# dms_sensor_board.net
KiCad netlist of a schematic drawn in EAGLE
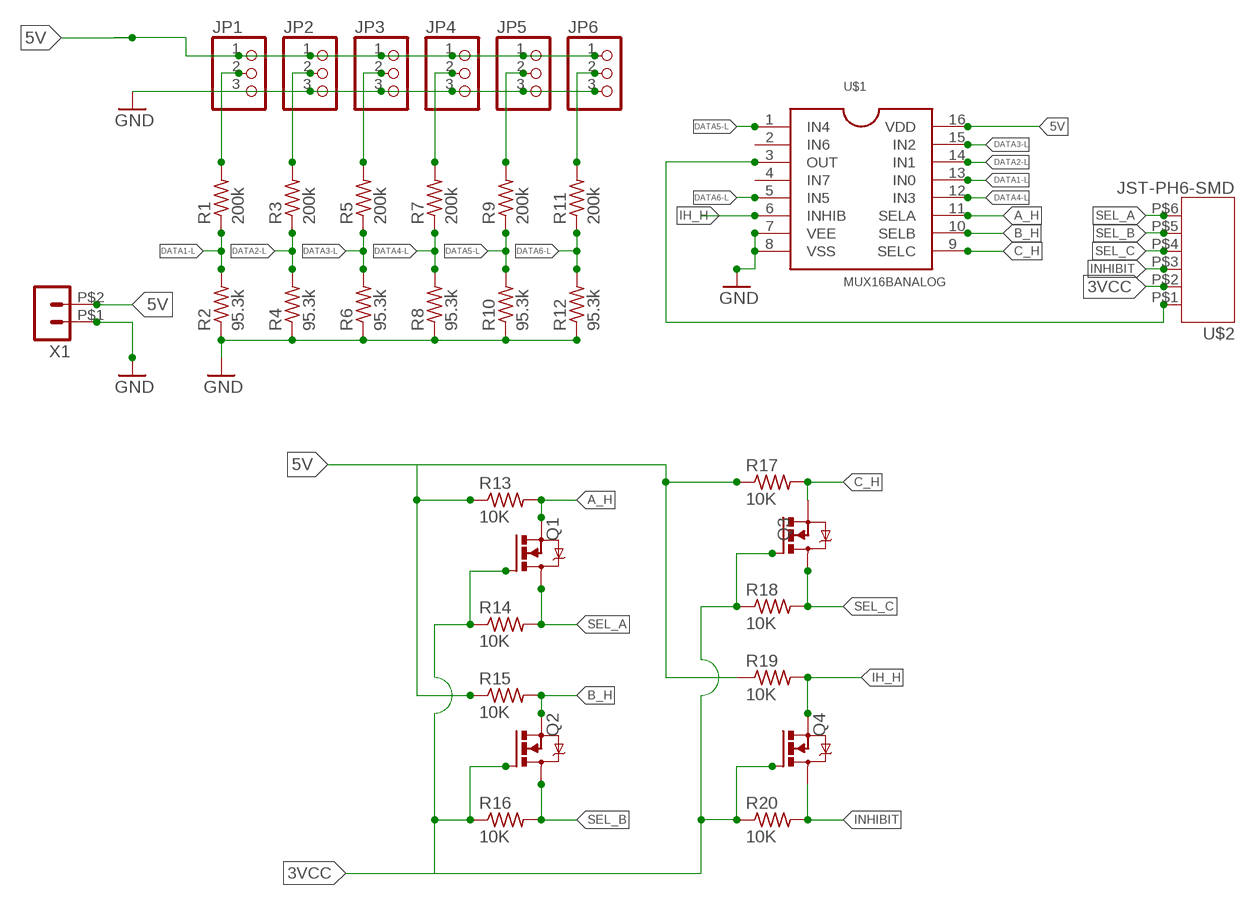
[diagram p0: schematic, sheet 1]

(export (version "E")
  (design (tool "Eeschema 10.0.6"))
  (components
    (comp (ref "JP1")
      (value "PINHD-1X03_2.00")
      (footprint "eagle-import:1X03M")
      (libsource (lib "eagle-import") (part "PINHD-1X03_2.00"))
    )
    (comp (ref "JP2")
      (value "PINHD-1X03_2.00")
      (footprint "eagle-import:1X03M")
      (libsource (lib "eagle-import") (part "PINHD-1X03_2.00"))
    )
    (comp (ref "JP3")
      (value "PINHD-1X03_2.00")
      (footprint "eagle-import:1X03M")
      (libsource (lib "eagle-import") (part "PINHD-1X03_2.00"))
    )
    (comp (ref "JP4")
      (value "PINHD-1X03_2.00")
      (footprint "eagle-import:1X03M")
      (libsource (lib "eagle-import") (part "PINHD-1X03_2.00"))
    )
    (comp (ref "JP5")
      (value "PINHD-1X03_2.00")
      (footprint "eagle-import:1X03M")
      (libsource (lib "eagle-import") (part "PINHD-1X03_2.00"))
    )
    (comp (ref "JP6")
      (value "PINHD-1X03_2.00")
      (footprint "eagle-import:1X03M")
      (libsource (lib "eagle-import") (part "PINHD-1X03_2.00"))
    )
    (comp (ref "Q1")
      (value "IRLML5203")
      (footprint "eagle-import:MICRO3")
      (libsource (lib "eagle-import") (part "IRLML5203"))
    )
    (comp (ref "Q2")
      (value "IRLML5203")
      (footprint "eagle-import:MICRO3")
      (libsource (lib "eagle-import") (part "IRLML5203"))
    )
    (comp (ref "Q3")
      (value "IRLML5203")
      (footprint "eagle-import:MICRO3")
      (libsource (lib "eagle-import") (part "IRLML5203"))
    )
    (comp (ref "Q4")
      (value "IRLML5203")
      (footprint "eagle-import:MICRO3")
      (libsource (lib "eagle-import") (part "IRLML5203"))
    )
    (comp (ref "R1")
      (value "200k")
      (footprint "eagle-import:R0805")
      (libsource (lib "eagle-import") (part "R-US_R0805"))
    )
    (comp (ref "R2")
      (value "95.3k")
      (footprint "eagle-import:R0805")
      (libsource (lib "eagle-import") (part "R-US_R0805"))
    )
    (comp (ref "R3")
      (value "200k")
      (footprint "eagle-import:R0805")
      (libsource (lib "eagle-import") (part "R-US_R0805"))
    )
    (comp (ref "R4")
      (value "95.3k")
      (footprint "eagle-import:R0805")
      (libsource (lib "eagle-import") (part "R-US_R0805"))
    )
    (comp (ref "R5")
      (value "200k")
      (footprint "eagle-import:R0805")
      (libsource (lib "eagle-import") (part "R-US_R0805"))
    )
    (comp (ref "R6")
      (value "95.3k")
      (footprint "eagle-import:R0805")
      (libsource (lib "eagle-import") (part "R-US_R0805"))
    )
    (comp (ref "R7")
      (value "200k")
      (footprint "eagle-import:R0805")
      (libsource (lib "eagle-import") (part "R-US_R0805"))
    )
    (comp (ref "R8")
      (value "95.3k")
      (footprint "eagle-import:R0805")
      (libsource (lib "eagle-import") (part "R-US_R0805"))
    )
    (comp (ref "R9")
      (value "200k")
      (footprint "eagle-import:R0805")
      (libsource (lib "eagle-import") (part "R-US_R0805"))
    )
    (comp (ref "R10")
      (value "95.3k")
      (footprint "eagle-import:R0805")
      (libsource (lib "eagle-import") (part "R-US_R0805"))
    )
    (comp (ref "R11")
      (value "200k")
      (footprint "eagle-import:R0805")
      (libsource (lib "eagle-import") (part "R-US_R0805"))
    )
    (comp (ref "R12")
      (value "95.3k")
      (footprint "eagle-import:R0805")
      (libsource (lib "eagle-import") (part "R-US_R0805"))
    )
    (comp (ref "R13")
      (value "10K")
      (footprint "eagle-import:R0805")
      (libsource (lib "eagle-import") (part "R-US_R0805"))
    )
    (comp (ref "R14")
      (value "10K")
      (footprint "eagle-import:R0805")
      (libsource (lib "eagle-import") (part "R-US_R0805"))
    )
    (comp (ref "R15")
      (value "10K")
      (footprint "eagle-import:R0805")
      (libsource (lib "eagle-import") (part "R-US_R0805"))
    )
    (comp (ref "R16")
      (value "10K")
      (footprint "eagle-import:R0805")
      (libsource (lib "eagle-import") (part "R-US_R0805"))
    )
    (comp (ref "R17")
      (value "10K")
      (footprint "eagle-import:R0805")
      (libsource (lib "eagle-import") (part "R-US_R0805"))
    )
    (comp (ref "R18")
      (value "10K")
      (footprint "eagle-import:R0805")
      (libsource (lib "eagle-import") (part "R-US_R0805"))
    )
    (comp (ref "R19")
      (value "10K")
      (footprint "eagle-import:R0805")
      (libsource (lib "eagle-import") (part "R-US_R0805"))
    )
    (comp (ref "R20")
      (value "10K")
      (footprint "eagle-import:R0805")
      (libsource (lib "eagle-import") (part "R-US_R0805"))
    )
    (comp (ref "U$1")
      (value "MUX16BANALOG")
      (footprint "eagle-import:SO16")
      (libsource (lib "eagle-import") (part "MUX16BANALOG"))
    )
    (comp (ref "U$2")
      (value "JST-PH6-SMD")
      (footprint "eagle-import:JST-PH6-SMD")
      (libsource (lib "eagle-import") (part "JST-PH6-SMD"))
    )
    (comp (ref "X1")
      (value "HEADER_POS2_43045-0206")
      (footprint "eagle-import:43045-0206")
      (libsource (lib "eagle-import") (part "HEADER_POS2_?43045-0206"))
    )
  )
  (nets
    (net (code "1") (name "3VCC") (class "Default")
      (node (ref "Q1") (pin "1") (pinfunction "G_1") (pintype "passive"))
      (node (ref "Q2") (pin "1") (pinfunction "G_1") (pintype "passive"))
      (node (ref "Q3") (pin "1") (pinfunction "G_1") (pintype "passive"))
      (node (ref "Q4") (pin "1") (pinfunction "G_1") (pintype "passive"))
      (node (ref "R14") (pin "1") (pinfunction "1_1") (pintype "passive"))
      (node (ref "R16") (pin "1") (pinfunction "1_1") (pintype "passive"))
      (node (ref "R18") (pin "1") (pinfunction "1_1") (pintype "passive"))
      (node (ref "R20") (pin "1") (pinfunction "1_1") (pintype "passive"))
      (node (ref "U$2") (pin "P$2") (pinfunction "2_P$2") (pintype "passive"))
    )
    (net (code "2") (name "5V") (class "Default")
      (node (ref "JP1") (pin "1") (pinfunction "1_1") (pintype "passive"))
      (node (ref "JP2") (pin "1") (pinfunction "1_1") (pintype "passive"))
      (node (ref "JP3") (pin "1") (pinfunction "1_1") (pintype "passive"))
      (node (ref "JP4") (pin "1") (pinfunction "1_1") (pintype "passive"))
      (node (ref "JP5") (pin "1") (pinfunction "1_1") (pintype "passive"))
      (node (ref "JP6") (pin "1") (pinfunction "1_1") (pintype "passive"))
      (node (ref "R13") (pin "1") (pinfunction "1_1") (pintype "passive"))
      (node (ref "R15") (pin "1") (pinfunction "1_1") (pintype "passive"))
      (node (ref "R17") (pin "1") (pinfunction "1_1") (pintype "passive"))
      (node (ref "R19") (pin "1") (pinfunction "1_1") (pintype "passive"))
      (node (ref "U$1") (pin "16") (pinfunction "VDD_16") (pintype "bidirectional"))
      (node (ref "X1") (pin "P$2") (pinfunction "2_P$2") (pintype "passive"))
    )
    (net (code "3") (name "A_H") (class "Default")
      (node (ref "Q1") (pin "2") (pinfunction "S_2") (pintype "passive"))
      (node (ref "R13") (pin "2") (pinfunction "2_2") (pintype "passive"))
      (node (ref "U$1") (pin "11") (pinfunction "SELA_11") (pintype "bidirectional"))
    )
    (net (code "4") (name "B_H") (class "Default")
      (node (ref "Q2") (pin "2") (pinfunction "S_2") (pintype "passive"))
      (node (ref "R15") (pin "2") (pinfunction "2_2") (pintype "passive"))
      (node (ref "U$1") (pin "10") (pinfunction "SELB_10") (pintype "bidirectional"))
    )
    (net (code "5") (name "C_H") (class "Default")
      (node (ref "Q3") (pin "2") (pinfunction "S_2") (pintype "passive"))
      (node (ref "R17") (pin "2") (pinfunction "2_2") (pintype "passive"))
      (node (ref "U$1") (pin "9") (pinfunction "SELC_9") (pintype "bidirectional"))
    )
    (net (code "6") (name "DATA1-L") (class "Default")
      (node (ref "R1") (pin "1") (pinfunction "1_1") (pintype "passive"))
      (node (ref "R2") (pin "2") (pinfunction "2_2") (pintype "passive"))
      (node (ref "U$1") (pin "13") (pinfunction "IN0_13") (pintype "bidirectional"))
    )
    (net (code "7") (name "DATA2-L") (class "Default")
      (node (ref "R3") (pin "1") (pinfunction "1_1") (pintype "passive"))
      (node (ref "R4") (pin "2") (pinfunction "2_2") (pintype "passive"))
      (node (ref "U$1") (pin "14") (pinfunction "IN1_14") (pintype "bidirectional"))
    )
    (net (code "8") (name "DATA3-L") (class "Default")
      (node (ref "R5") (pin "1") (pinfunction "1_1") (pintype "passive"))
      (node (ref "R6") (pin "2") (pinfunction "2_2") (pintype "passive"))
      (node (ref "U$1") (pin "15") (pinfunction "IN2_15") (pintype "bidirectional"))
    )
    (net (code "9") (name "DATA4-L") (class "Default")
      (node (ref "R7") (pin "1") (pinfunction "1_1") (pintype "passive"))
      (node (ref "R8") (pin "2") (pinfunction "2_2") (pintype "passive"))
      (node (ref "U$1") (pin "12") (pinfunction "IN3_12") (pintype "bidirectional"))
    )
    (net (code "10") (name "DATA5-L") (class "Default")
      (node (ref "R10") (pin "2") (pinfunction "2_2") (pintype "passive"))
      (node (ref "R9") (pin "1") (pinfunction "1_1") (pintype "passive"))
      (node (ref "U$1") (pin "1") (pinfunction "IN4_1") (pintype "bidirectional"))
    )
    (net (code "11") (name "DATA6-L") (class "Default")
      (node (ref "R11") (pin "1") (pinfunction "1_1") (pintype "passive"))
      (node (ref "R12") (pin "2") (pinfunction "2_2") (pintype "passive"))
      (node (ref "U$1") (pin "5") (pinfunction "IN5_5") (pintype "bidirectional"))
    )
    (net (code "12") (name "GND") (class "Default")
      (node (ref "JP1") (pin "3") (pinfunction "3_3") (pintype "passive"))
      (node (ref "JP2") (pin "3") (pinfunction "3_3") (pintype "passive"))
      (node (ref "JP3") (pin "3") (pinfunction "3_3") (pintype "passive"))
      (node (ref "JP4") (pin "3") (pinfunction "3_3") (pintype "passive"))
      (node (ref "JP5") (pin "3") (pinfunction "3_3") (pintype "passive"))
      (node (ref "JP6") (pin "3") (pinfunction "3_3") (pintype "passive"))
      (node (ref "R10") (pin "1") (pinfunction "1_1") (pintype "passive"))
      (node (ref "R12") (pin "1") (pinfunction "1_1") (pintype "passive"))
      (node (ref "R2") (pin "1") (pinfunction "1_1") (pintype "passive"))
      (node (ref "R4") (pin "1") (pinfunction "1_1") (pintype "passive"))
      (node (ref "R6") (pin "1") (pinfunction "1_1") (pintype "passive"))
      (node (ref "R8") (pin "1") (pinfunction "1_1") (pintype "passive"))
      (node (ref "U$1") (pin "7") (pinfunction "VEE_7") (pintype "bidirectional"))
      (node (ref "U$1") (pin "8") (pinfunction "VSS_8") (pintype "bidirectional"))
      (node (ref "X1") (pin "P$1") (pinfunction "1_P$1") (pintype "passive"))
    )
    (net (code "13") (name "IH_H") (class "Default")
      (node (ref "Q4") (pin "2") (pinfunction "S_2") (pintype "passive"))
      (node (ref "R19") (pin "2") (pinfunction "2_2") (pintype "passive"))
      (node (ref "U$1") (pin "6") (pinfunction "INHIB_6") (pintype "bidirectional"))
    )
    (net (code "14") (name "INHIBIT") (class "Default")
      (node (ref "Q4") (pin "3") (pinfunction "D_3") (pintype "passive"))
      (node (ref "R20") (pin "2") (pinfunction "2_2") (pintype "passive"))
      (node (ref "U$2") (pin "P$3") (pinfunction "3_P$3") (pintype "passive"))
    )
    (net (code "15") (name "Net-(JP1-Pad2)") (class "Default")
      (node (ref "JP1") (pin "2") (pinfunction "2_2") (pintype "passive"))
      (node (ref "R1") (pin "2") (pinfunction "2_2") (pintype "passive"))
    )
    (net (code "16") (name "Net-(JP2-Pad2)") (class "Default")
      (node (ref "JP2") (pin "2") (pinfunction "2_2") (pintype "passive"))
      (node (ref "R3") (pin "2") (pinfunction "2_2") (pintype "passive"))
    )
    (net (code "17") (name "Net-(JP3-Pad2)") (class "Default")
      (node (ref "JP3") (pin "2") (pinfunction "2_2") (pintype "passive"))
      (node (ref "R5") (pin "2") (pinfunction "2_2") (pintype "passive"))
    )
    (net (code "18") (name "Net-(JP4-Pad2)") (class "Default")
      (node (ref "JP4") (pin "2") (pinfunction "2_2") (pintype "passive"))
      (node (ref "R7") (pin "2") (pinfunction "2_2") (pintype "passive"))
    )
    (net (code "19") (name "Net-(JP5-Pad2)") (class "Default")
      (node (ref "JP5") (pin "2") (pinfunction "2_2") (pintype "passive"))
      (node (ref "R9") (pin "2") (pinfunction "2_2") (pintype "passive"))
    )
    (net (code "20") (name "Net-(JP6-Pad2)") (class "Default")
      (node (ref "JP6") (pin "2") (pinfunction "2_2") (pintype "passive"))
      (node (ref "R11") (pin "2") (pinfunction "2_2") (pintype "passive"))
    )
    (net (code "21") (name "Net-(U$1-OUT)") (class "Default")
      (node (ref "U$1") (pin "3") (pinfunction "OUT_3") (pintype "bidirectional"))
      (node (ref "U$2") (pin "P$1") (pinfunction "1_P$1") (pintype "passive"))
    )
    (net (code "22") (name "SEL_A") (class "Default")
      (node (ref "Q1") (pin "3") (pinfunction "D_3") (pintype "passive"))
      (node (ref "R14") (pin "2") (pinfunction "2_2") (pintype "passive"))
      (node (ref "U$2") (pin "P$6") (pinfunction "6_P$6") (pintype "passive"))
    )
    (net (code "23") (name "SEL_B") (class "Default")
      (node (ref "Q2") (pin "3") (pinfunction "D_3") (pintype "passive"))
      (node (ref "R16") (pin "2") (pinfunction "2_2") (pintype "passive"))
      (node (ref "U$2") (pin "P$5") (pinfunction "5_P$5") (pintype "passive"))
    )
    (net (code "24") (name "SEL_C") (class "Default")
      (node (ref "Q3") (pin "3") (pinfunction "D_3") (pintype "passive"))
      (node (ref "R18") (pin "2") (pinfunction "2_2") (pintype "passive"))
      (node (ref "U$2") (pin "P$4") (pinfunction "4_P$4") (pintype "passive"))
    )
    (net (code "25") (name "unconnected-(U$1-IN6-Pad2)") (class "Default")
      (node (ref "U$1") (pin "2") (pinfunction "IN6_2") (pintype "bidirectional"))
    )
    (net (code "26") (name "unconnected-(U$1-IN7-Pad4)") (class "Default")
      (node (ref "U$1") (pin "4") (pinfunction "IN7_4") (pintype "bidirectional"))
    )
  )
)
